# FE.net
KiCad netlist of a schematic drawn in Altium Designer
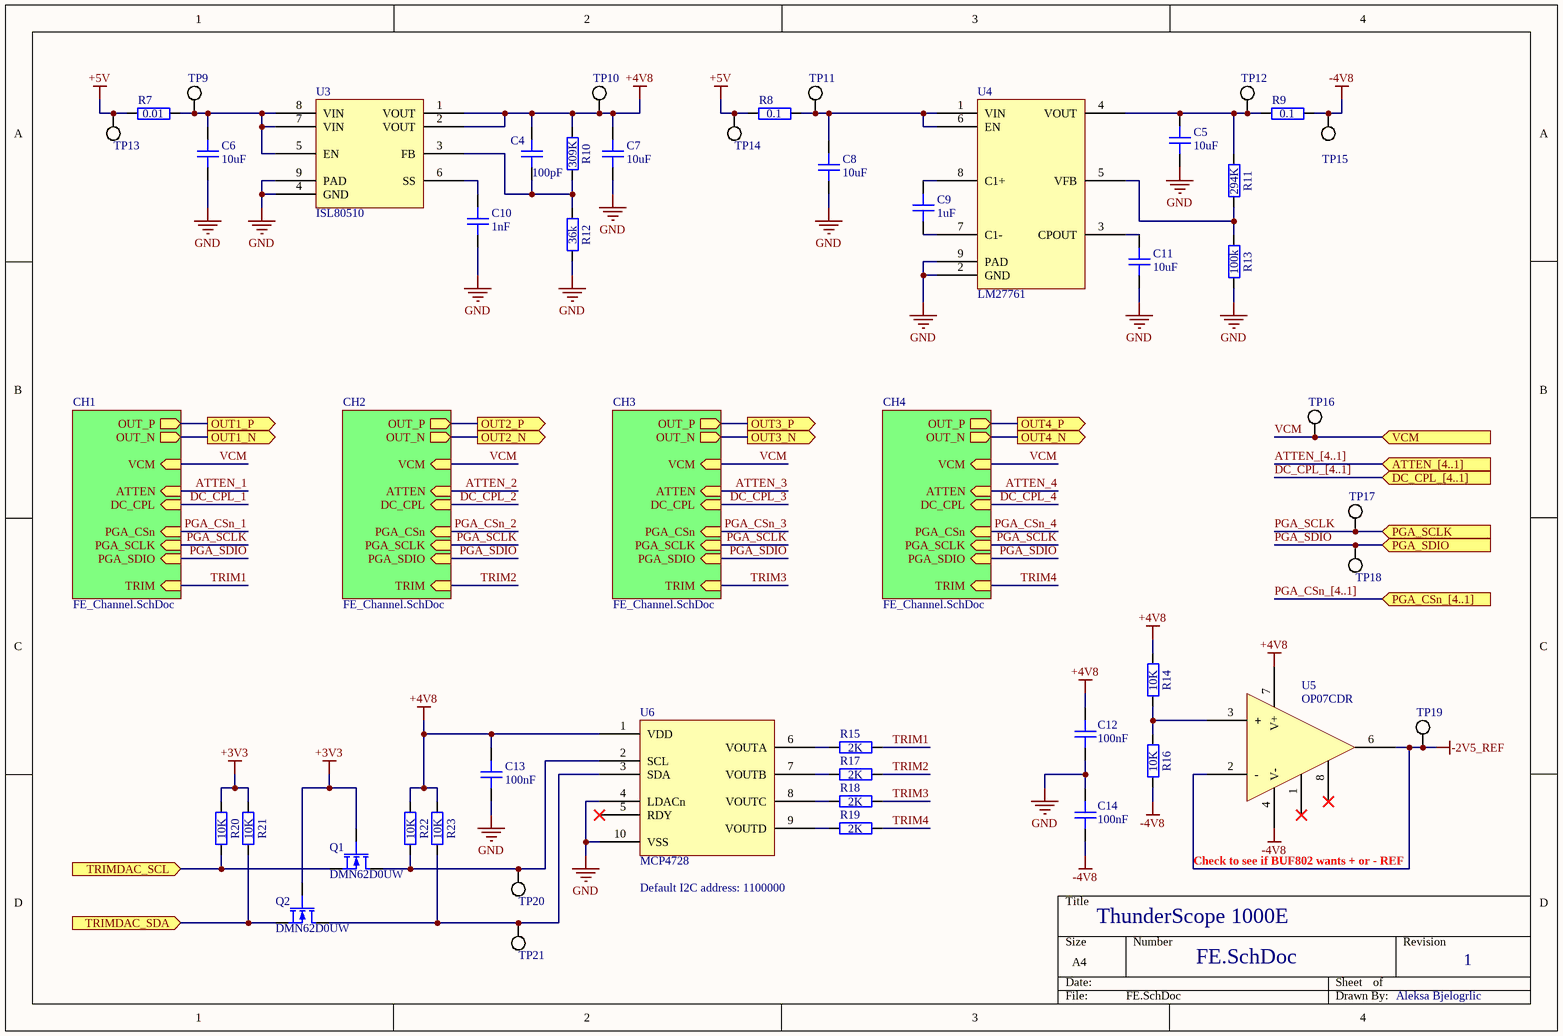
[diagram p0: FE.SchDoc]

(export (version "E")
  (design (tool "Eeschema 10.0.6"))
  (components
    (comp (ref "C4")
      (value "100pF")
      (footprint "GEN_C_0402")
      (libsource (lib "DSO") (part "CAP 100pF 50V C0G 0402"))
    )
    (comp (ref "C5")
      (value "10uF")
      (footprint "GEN_C_0603")
      (libsource (lib "DSO") (part "CAP 10uF 10V X5R 0603"))
    )
    (comp (ref "C6")
      (value "10uF")
      (footprint "GEN_C_0603")
      (libsource (lib "DSO") (part "CAP 10uF 10V X5R 0603"))
    )
    (comp (ref "C7")
      (value "10uF")
      (footprint "GEN_C_0603")
      (libsource (lib "DSO") (part "CAP 10uF 10V X5R 0603"))
    )
    (comp (ref "C8")
      (value "10uF")
      (footprint "GEN_C_0603")
      (libsource (lib "DSO") (part "CAP 10uF 10V X5R 0603"))
    )
    (comp (ref "C9")
      (value "1uF")
      (footprint "GEN_C_0402")
      (libsource (lib "DSO") (part "CAP 1uF 25V X5R 0402"))
    )
    (comp (ref "C10")
      (value "1nF")
      (footprint "GEN_C_0402")
      (libsource (lib "DSO") (part "CAP 1nF 50V C0G 0402"))
    )
    (comp (ref "C11")
      (value "10uF")
      (footprint "GEN_C_0603")
      (libsource (lib "DSO") (part "CAP 10uF 10V X5R 0603"))
    )
    (comp (ref "C12")
      (value "100nF")
      (footprint "GEN_C_0402")
      (libsource (lib "DSO") (part "CAP 100nF 16V X7R 0402"))
    )
    (comp (ref "C13")
      (value "100nF")
      (footprint "GEN_C_0402")
      (libsource (lib "DSO") (part "CAP 100nF 16V X7R 0402"))
    )
    (comp (ref "C14")
      (value "100nF")
      (footprint "GEN_C_0402")
      (libsource (lib "DSO") (part "CAP 100nF 16V X7R 0402"))
    )
    (comp (ref "Q1")
      (value "DMN62D0UW")
      (footprint "GEN_SOT_323")
      (libsource (lib "DSO") (part "NMOS DMN62D0UW"))
    )
    (comp (ref "Q2")
      (value "DMN62D0UW")
      (footprint "GEN_SOT_323")
      (libsource (lib "DSO") (part "NMOS DMN62D0UW"))
    )
    (comp (ref "R7")
      (value "0.01")
      (footprint "GEN_R_0603")
      (fields (field (name "TOLERANCE") "1%"))
      (libsource (lib "DSO") (part "RES 0.01 OHM 1% 1/4W 0603"))
    )
    (comp (ref "R8")
      (value "0.1")
      (footprint "GEN_R_0402")
      (fields (field (name "TOLERANCE") "1%"))
      (libsource (lib "DSO") (part "RES 0.1 OHM 1% 1/6W 0402"))
    )
    (comp (ref "R9")
      (value "0.1")
      (footprint "GEN_R_0402")
      (fields (field (name "TOLERANCE") "1%"))
      (libsource (lib "DSO") (part "RES 0.1 OHM 1% 1/6W 0402"))
    )
    (comp (ref "R10")
      (value "309K")
      (footprint "GEN_R_0402")
      (fields (field (name "TOLERANCE") "1%"))
      (libsource (lib "DSO") (part "RES 309K OHM 1% 1/16W 0402"))
    )
    (comp (ref "R11")
      (value "294K")
      (footprint "GEN_R_0402")
      (fields (field (name "TOLERANCE") "1%"))
      (libsource (lib "DSO") (part "RES 294K OHM 1% 1/16W 0402"))
    )
    (comp (ref "R12")
      (value "36k")
      (footprint "GEN_R_0402")
      (fields (field (name "TOLERANCE") "1%"))
      (libsource (lib "DSO") (part "RES 36K OHM 1% 1/16W 0402"))
    )
    (comp (ref "R13")
      (value "100k")
      (footprint "GEN_R_0402")
      (fields (field (name "TOLERANCE") "1%"))
      (libsource (lib "DSO") (part "RES 100K OHM 1% 1/10W 0402"))
    )
    (comp (ref "R14")
      (value "10K")
      (footprint "GEN_R_0402")
      (fields (field (name "TOLERANCE") "1%"))
      (libsource (lib "") (part "RES 10K OHM 1% 1/10W 0402_1"))
    )
    (comp (ref "R15")
      (value "2K")
      (footprint "GEN_R_0402")
      (fields (field (name "TOLERANCE") "1%"))
      (libsource (lib "DSO") (part "RES 2K OHM 1% 1/16W 0402"))
    )
    (comp (ref "R16")
      (value "10K")
      (footprint "GEN_R_0402")
      (fields (field (name "TOLERANCE") "1%"))
      (libsource (lib "") (part "RES 10K OHM 1% 1/10W 0402_1"))
    )
    (comp (ref "R17")
      (value "2K")
      (footprint "GEN_R_0402")
      (fields (field (name "TOLERANCE") "1%"))
      (libsource (lib "DSO") (part "RES 2K OHM 1% 1/16W 0402"))
    )
    (comp (ref "R18")
      (value "2K")
      (footprint "GEN_R_0402")
      (fields (field (name "TOLERANCE") "1%"))
      (libsource (lib "DSO") (part "RES 2K OHM 1% 1/16W 0402"))
    )
    (comp (ref "R19")
      (value "2K")
      (footprint "GEN_R_0402")
      (fields (field (name "TOLERANCE") "1%"))
      (libsource (lib "DSO") (part "RES 2K OHM 1% 1/16W 0402"))
    )
    (comp (ref "R20")
      (value "10K")
      (footprint "GEN_R_0402")
      (fields (field (name "TOLERANCE") "1%"))
      (libsource (lib "DSO") (part "RES 10K OHM 1% 1/10W 0402"))
    )
    (comp (ref "R21")
      (value "10K")
      (footprint "GEN_R_0402")
      (fields (field (name "TOLERANCE") "1%"))
      (libsource (lib "DSO") (part "RES 10K OHM 1% 1/10W 0402"))
    )
    (comp (ref "R22")
      (value "10K")
      (footprint "GEN_R_0402")
      (fields (field (name "TOLERANCE") "1%"))
      (libsource (lib "DSO") (part "RES 10K OHM 1% 1/10W 0402"))
    )
    (comp (ref "R23")
      (value "10K")
      (footprint "GEN_R_0402")
      (fields (field (name "TOLERANCE") "1%"))
      (libsource (lib "DSO") (part "RES 10K OHM 1% 1/10W 0402"))
    )
    (comp (ref "TP9") (value "PCB") (footprint "GEN_TP_PCB") (libsource (lib "DSO") (part "TP PCB 1mm")))
    (comp (ref "TP10") (value "PCB") (footprint "GEN_TP_PCB") (libsource (lib "DSO") (part "TP PCB 1mm")))
    (comp (ref "TP11") (value "PCB") (footprint "GEN_TP_PCB") (libsource (lib "DSO") (part "TP PCB 1mm")))
    (comp (ref "TP12") (value "PCB") (footprint "GEN_TP_PCB") (libsource (lib "DSO") (part "TP PCB 1mm")))
    (comp (ref "TP13") (value "PCB") (footprint "GEN_TP_PCB") (libsource (lib "DSO") (part "TP PCB 1mm")))
    (comp (ref "TP14") (value "PCB") (footprint "GEN_TP_PCB") (libsource (lib "DSO") (part "TP PCB 1mm")))
    (comp (ref "TP15") (value "PCB") (footprint "GEN_TP_PCB") (libsource (lib "DSO") (part "TP PCB 1mm")))
    (comp (ref "TP16") (value "PCB") (footprint "GEN_TP_PCB") (libsource (lib "DSO") (part "TP PCB 1mm")))
    (comp (ref "TP17") (value "PCB") (footprint "GEN_TP_PCB") (libsource (lib "DSO") (part "TP PCB 1mm")))
    (comp (ref "TP18") (value "PCB") (footprint "GEN_TP_PCB") (libsource (lib "DSO") (part "TP PCB 1mm")))
    (comp (ref "TP19") (value "PCB") (footprint "GEN_TP_PCB") (libsource (lib "DSO") (part "TP PCB 1mm")))
    (comp (ref "TP20") (value "PCB") (footprint "GEN_TP_PCB") (libsource (lib "DSO") (part "TP PCB 1mm")))
    (comp (ref "TP21") (value "PCB") (footprint "GEN_TP_PCB") (libsource (lib "DSO") (part "TP PCB 1mm")))
    (comp (ref "U3")
      (value "ISL80510")
      (footprint "REN_DFN_ISL80510")
      (libsource (lib "DSO") (part "IC LDO ISL80510"))
    )
    (comp (ref "U4")
      (value "LM27761")
      (footprint "TI_WSON8_DSG0008A")
      (libsource (lib "DSO") (part "IC CPUMP LM27761"))
    )
    (comp (ref "U5")
      (value "OP07CDR")
      (footprint "TI_SOIC8_D0008A")
      (libsource (lib "DSO") (part "IC OPAMP OP07CDR"))
    )
    (comp (ref "U6")
      (value "MCP4728")
      (footprint "MC_MSOP10_UN")
      (libsource (lib "DSO") (part "IC DAC QUAD MCP4728"))
    )
  )
  (nets
    (net (code "1") (name "+3V3") (class "Default")
      (node (ref "Q1") (pin "2") (pinfunction "G_2") (pintype "passive"))
      (node (ref "Q2") (pin "2") (pinfunction "G_2") (pintype "passive"))
      (node (ref "R20") (pin "2") (pinfunction "2_2") (pintype "passive"))
      (node (ref "R21") (pin "2") (pinfunction "2_2") (pintype "passive"))
    )
    (net (code "2") (name "+4V8") (class "Default")
      (node (ref "C12") (pin "1") (pinfunction "1_1") (pintype "passive"))
      (node (ref "C13") (pin "2") (pinfunction "2_2") (pintype "passive"))
      (node (ref "C4") (pin "2") (pinfunction "2_2") (pintype "passive"))
      (node (ref "C7") (pin "2") (pinfunction "2_2") (pintype "passive"))
      (node (ref "R10") (pin "2") (pinfunction "2_2") (pintype "passive"))
      (node (ref "R14") (pin "2") (pinfunction "2_2") (pintype "passive"))
      (node (ref "R22") (pin "2") (pinfunction "2_2") (pintype "passive"))
      (node (ref "R23") (pin "2") (pinfunction "2_2") (pintype "passive"))
      (node (ref "TP10") (pin "1") (pinfunction "1_1") (pintype "passive"))
      (node (ref "U3") (pin "1") (pinfunction "VOUT_1") (pintype "power_in"))
      (node (ref "U3") (pin "2") (pinfunction "VOUT_2") (pintype "power_in"))
      (node (ref "U5") (pin "7") (pinfunction "V+_7") (pintype "passive"))
      (node (ref "U6") (pin "1") (pinfunction "VDD_1") (pintype "power_in"))
    )
    (net (code "3") (name "+5V") (class "Default")
      (node (ref "R7") (pin "1") (pinfunction "1_1") (pintype "passive"))
      (node (ref "R8") (pin "1") (pinfunction "1_1") (pintype "passive"))
      (node (ref "TP13") (pin "1") (pinfunction "1_1") (pintype "passive"))
      (node (ref "TP14") (pin "1") (pinfunction "1_1") (pintype "passive"))
    )
    (net (code "4") (name "-2V5_REF") (class "Default")
      (node (ref "TP19") (pin "1") (pinfunction "1_1") (pintype "passive"))
      (node (ref "U5") (pin "2") (pinfunction "-_2") (pintype "passive"))
      (node (ref "U5") (pin "6") (pinfunction "OUT_6") (pintype "passive"))
    )
    (net (code "5") (name "-4V8") (class "Default")
      (node (ref "C14") (pin "2") (pinfunction "2_2") (pintype "passive"))
      (node (ref "R16") (pin "1") (pinfunction "1_1") (pintype "passive"))
      (node (ref "R9") (pin "2") (pinfunction "2_2") (pintype "passive"))
      (node (ref "TP15") (pin "1") (pinfunction "1_1") (pintype "passive"))
      (node (ref "U5") (pin "4") (pinfunction "V-_4") (pintype "passive"))
    )
    (net (code "29") (name "/PGA_SCLK") (class "Default")
      (node (ref "TP17") (pin "1") (pinfunction "1_1") (pintype "passive"))
    )
    (net (code "30") (name "/PGA_SDIO") (class "Default")
      (node (ref "TP18") (pin "1") (pinfunction "1_1") (pintype "passive"))
    )
    (net (code "31") (name "/TRIM1") (class "Default")
      (node (ref "R15") (pin "1") (pinfunction "1_1") (pintype "passive"))
    )
    (net (code "32") (name "/TRIM2") (class "Default")
      (node (ref "R17") (pin "1") (pinfunction "1_1") (pintype "passive"))
    )
    (net (code "33") (name "/TRIM3") (class "Default")
      (node (ref "R18") (pin "1") (pinfunction "1_1") (pintype "passive"))
    )
    (net (code "34") (name "/TRIM4") (class "Default")
      (node (ref "R19") (pin "1") (pinfunction "1_1") (pintype "passive"))
    )
    (net (code "35") (name "/TRIMDAC_SCL") (class "Default")
      (node (ref "Q1") (pin "3") (pinfunction "S_3") (pintype "passive"))
      (node (ref "R20") (pin "1") (pinfunction "1_1") (pintype "passive"))
    )
    (net (code "36") (name "/TRIMDAC_SDA") (class "Default")
      (node (ref "Q2") (pin "3") (pinfunction "S_3") (pintype "passive"))
      (node (ref "R21") (pin "1") (pinfunction "1_1") (pintype "passive"))
    )
    (net (code "37") (name "/VCM") (class "Default")
      (node (ref "TP16") (pin "1") (pinfunction "1_1") (pintype "passive"))
    )
    (net (code "38") (name "GND") (class "Default")
      (node (ref "C10") (pin "1") (pinfunction "1_1") (pintype "passive"))
      (node (ref "C11") (pin "1") (pinfunction "1_1") (pintype "passive"))
      (node (ref "C12") (pin "2") (pinfunction "2_2") (pintype "passive"))
      (node (ref "C13") (pin "1") (pinfunction "1_1") (pintype "passive"))
      (node (ref "C14") (pin "1") (pinfunction "1_1") (pintype "passive"))
      (node (ref "C5") (pin "1") (pinfunction "1_1") (pintype "passive"))
      (node (ref "C6") (pin "1") (pinfunction "1_1") (pintype "passive"))
      (node (ref "C7") (pin "1") (pinfunction "1_1") (pintype "passive"))
      (node (ref "C8") (pin "1") (pinfunction "1_1") (pintype "passive"))
      (node (ref "R12") (pin "1") (pinfunction "1_1") (pintype "passive"))
      (node (ref "R13") (pin "1") (pinfunction "1_1") (pintype "passive"))
      (node (ref "U3") (pin "4") (pinfunction "GND_4") (pintype "power_in"))
      (node (ref "U3") (pin "9") (pinfunction "PAD_9") (pintype "passive"))
      (node (ref "U4") (pin "2") (pinfunction "GND_2") (pintype "power_in"))
      (node (ref "U4") (pin "9") (pinfunction "PAD_9") (pintype "power_in"))
      (node (ref "U6") (pin "10") (pinfunction "VSS_10") (pintype "power_in"))
      (node (ref "U6") (pin "4") (pinfunction "LDACn_4") (pintype "passive"))
    )
    (net (code "39") (name "Net-(Q1-D)") (class "Default")
      (node (ref "Q1") (pin "1") (pinfunction "D_1") (pintype "passive"))
      (node (ref "R22") (pin "1") (pinfunction "1_1") (pintype "passive"))
      (node (ref "TP20") (pin "1") (pinfunction "1_1") (pintype "passive"))
      (node (ref "U6") (pin "2") (pinfunction "SCL_2") (pintype "passive"))
    )
    (net (code "40") (name "Net-(Q2-D)") (class "Default")
      (node (ref "Q2") (pin "1") (pinfunction "D_1") (pintype "passive"))
      (node (ref "R23") (pin "1") (pinfunction "1_1") (pintype "passive"))
      (node (ref "TP21") (pin "1") (pinfunction "1_1") (pintype "passive"))
      (node (ref "U6") (pin "3") (pinfunction "SDA_3") (pintype "passive"))
    )
    (net (code "41") (name "Net-(U3-EN)") (class "Default")
      (node (ref "C6") (pin "2") (pinfunction "2_2") (pintype "passive"))
      (node (ref "R7") (pin "2") (pinfunction "2_2") (pintype "passive"))
      (node (ref "TP9") (pin "1") (pinfunction "1_1") (pintype "passive"))
      (node (ref "U3") (pin "5") (pinfunction "EN_5") (pintype "passive"))
      (node (ref "U3") (pin "7") (pinfunction "VIN_7") (pintype "power_in"))
      (node (ref "U3") (pin "8") (pinfunction "VIN_8") (pintype "power_in"))
    )
    (net (code "42") (name "Net-(U3-FB)") (class "Default")
      (node (ref "C4") (pin "1") (pinfunction "1_1") (pintype "passive"))
      (node (ref "R10") (pin "1") (pinfunction "1_1") (pintype "passive"))
      (node (ref "R12") (pin "2") (pinfunction "2_2") (pintype "passive"))
      (node (ref "U3") (pin "3") (pinfunction "FB_3") (pintype "passive"))
    )
    (net (code "43") (name "Net-(U3-SS)") (class "Default")
      (node (ref "C10") (pin "2") (pinfunction "2_2") (pintype "passive"))
      (node (ref "U3") (pin "6") (pinfunction "SS_6") (pintype "passive"))
    )
    (net (code "44") (name "Net-(U4-C1+)") (class "Default")
      (node (ref "C9") (pin "2") (pinfunction "2_2") (pintype "passive"))
      (node (ref "U4") (pin "8") (pinfunction "C1+_8") (pintype "passive"))
    )
    (net (code "45") (name "Net-(U4-C1-)") (class "Default")
      (node (ref "C9") (pin "1") (pinfunction "1_1") (pintype "passive"))
      (node (ref "U4") (pin "7") (pinfunction "C1-_7") (pintype "passive"))
    )
    (net (code "46") (name "Net-(U4-CPOUT)") (class "Default")
      (node (ref "C11") (pin "2") (pinfunction "2_2") (pintype "passive"))
      (node (ref "U4") (pin "3") (pinfunction "CPOUT_3") (pintype "passive"))
    )
    (net (code "47") (name "Net-(U4-EN)") (class "Default")
      (node (ref "C8") (pin "2") (pinfunction "2_2") (pintype "passive"))
      (node (ref "R8") (pin "2") (pinfunction "2_2") (pintype "passive"))
      (node (ref "TP11") (pin "1") (pinfunction "1_1") (pintype "passive"))
      (node (ref "U4") (pin "1") (pinfunction "VIN_1") (pintype "power_in"))
      (node (ref "U4") (pin "6") (pinfunction "EN_6") (pintype "passive"))
    )
    (net (code "48") (name "Net-(U4-VFB)") (class "Default")
      (node (ref "R11") (pin "1") (pinfunction "1_1") (pintype "passive"))
      (node (ref "R13") (pin "2") (pinfunction "2_2") (pintype "passive"))
      (node (ref "U4") (pin "5") (pinfunction "VFB_5") (pintype "passive"))
    )
    (net (code "49") (name "Net-(U4-VOUT)") (class "Default")
      (node (ref "C5") (pin "2") (pinfunction "2_2") (pintype "passive"))
      (node (ref "R11") (pin "2") (pinfunction "2_2") (pintype "passive"))
      (node (ref "R9") (pin "1") (pinfunction "1_1") (pintype "passive"))
      (node (ref "TP12") (pin "1") (pinfunction "1_1") (pintype "passive"))
      (node (ref "U4") (pin "4") (pinfunction "VOUT_4") (pintype "power_in"))
    )
    (net (code "50") (name "Net-(U5-+)") (class "Default")
      (node (ref "R14") (pin "1") (pinfunction "1_1") (pintype "passive"))
      (node (ref "R16") (pin "2") (pinfunction "2_2") (pintype "passive"))
      (node (ref "U5") (pin "3") (pinfunction "+_3") (pintype "passive"))
    )
    (net (code "51") (name "Net-(U6-VOUTA)") (class "Default")
      (node (ref "R15") (pin "2") (pinfunction "2_2") (pintype "passive"))
      (node (ref "U6") (pin "6") (pinfunction "VOUTA_6") (pintype "passive"))
    )
    (net (code "52") (name "Net-(U6-VOUTB)") (class "Default")
      (node (ref "R17") (pin "2") (pinfunction "2_2") (pintype "passive"))
      (node (ref "U6") (pin "7") (pinfunction "VOUTB_7") (pintype "passive"))
    )
    (net (code "53") (name "Net-(U6-VOUTC)") (class "Default")
      (node (ref "R18") (pin "2") (pinfunction "2_2") (pintype "passive"))
      (node (ref "U6") (pin "8") (pinfunction "VOUTC_8") (pintype "passive"))
    )
    (net (code "54") (name "Net-(U6-VOUTD)") (class "Default")
      (node (ref "R19") (pin "2") (pinfunction "2_2") (pintype "passive"))
      (node (ref "U6") (pin "9") (pinfunction "VOUTD_9") (pintype "passive"))
    )
    (net (code "55") (name "unconnected-(U5-N1-Pad1)") (class "Default")
      (node (ref "U5") (pin "1") (pinfunction "N1_1") (pintype "passive+no_connect"))
    )
    (net (code "56") (name "unconnected-(U5-N2-Pad8)") (class "Default")
      (node (ref "U5") (pin "8") (pinfunction "N2_8") (pintype "passive+no_connect"))
    )
    (net (code "57") (name "unconnected-(U6-RDY-Pad5)") (class "Default")
      (node (ref "U6") (pin "5") (pinfunction "RDY_5") (pintype "passive+no_connect"))
    )
  )
)
